# tx_v2.net
KiCad netlist of a schematic drawn in EAGLE
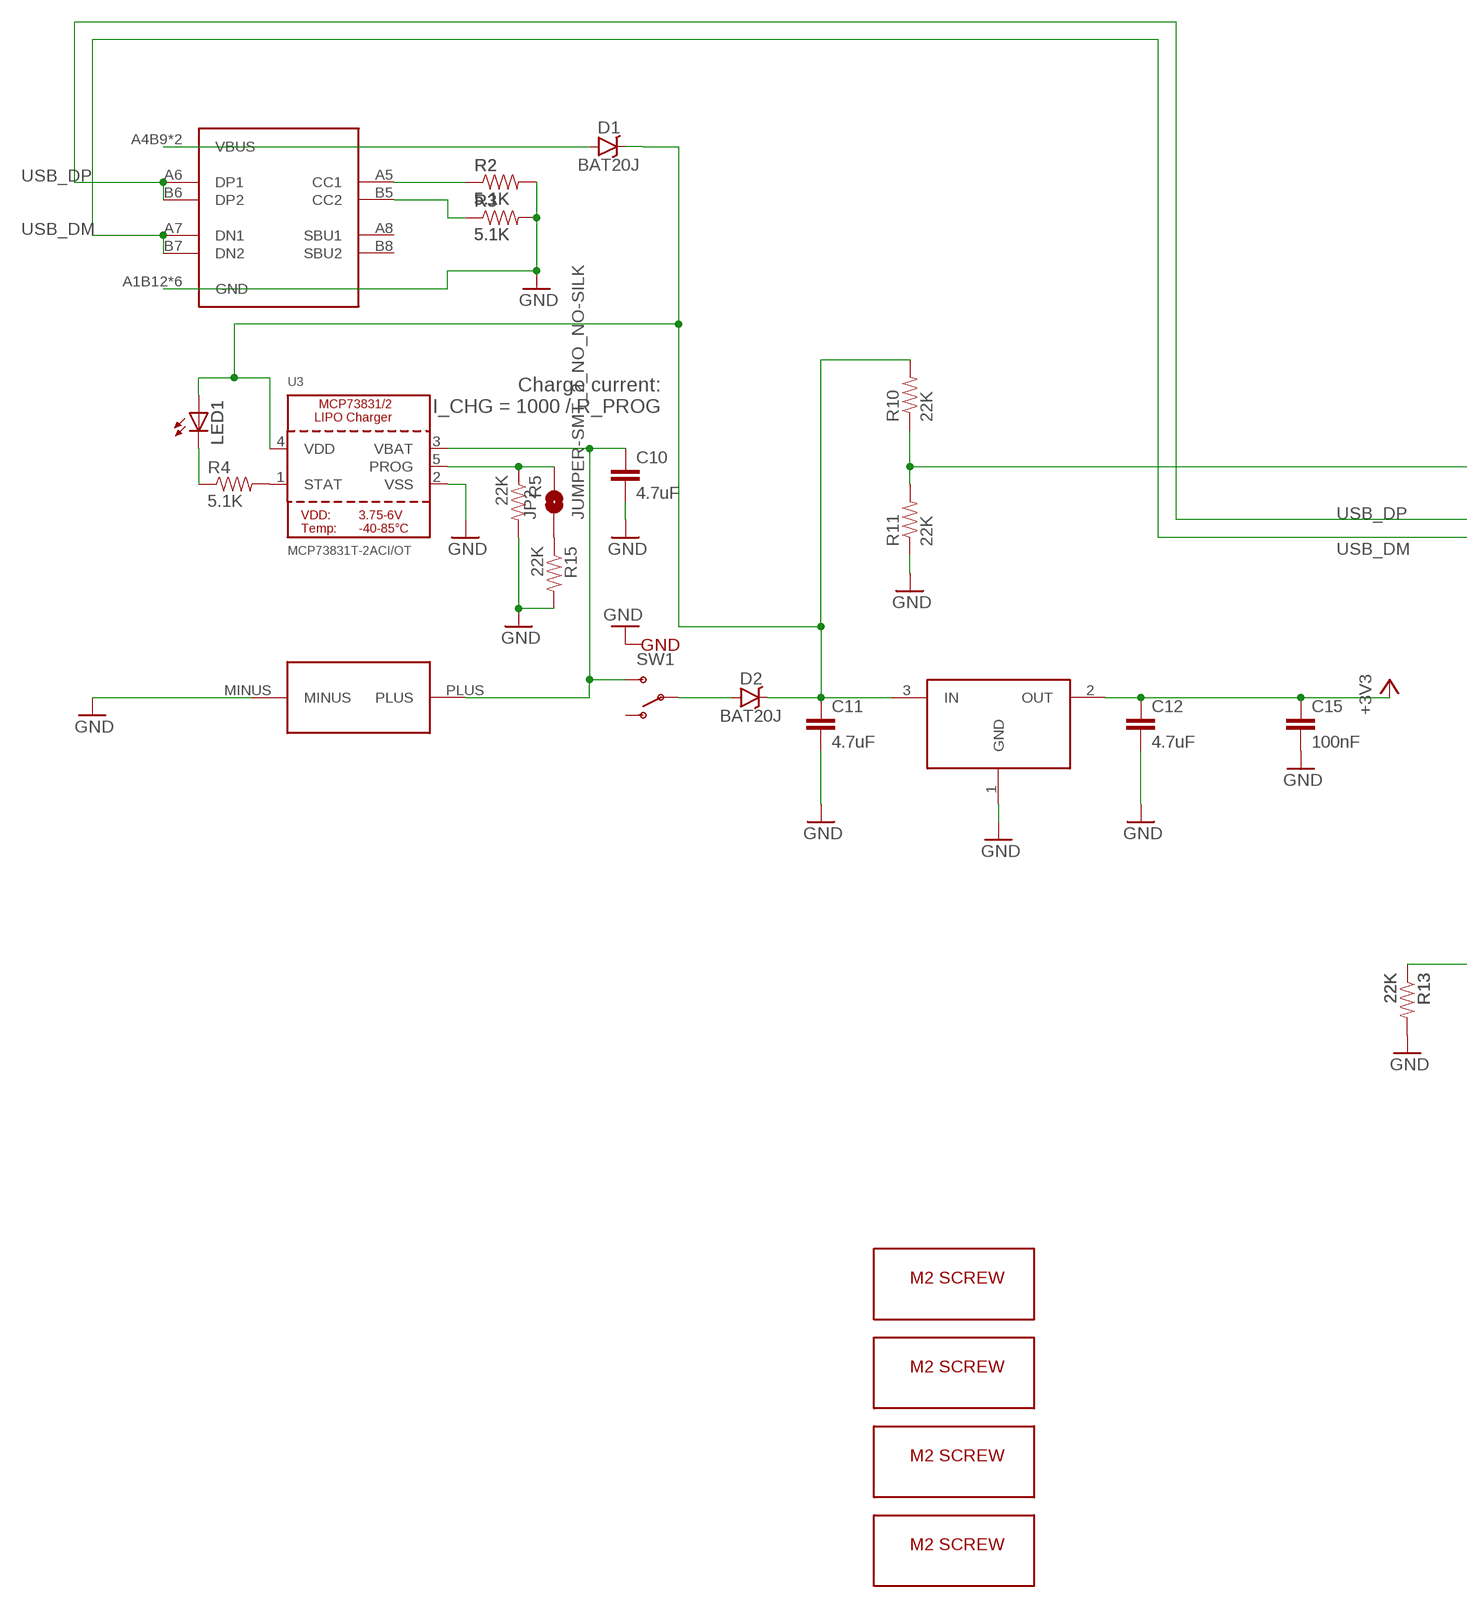
[diagram p0: schematic, sheet 1, part 1 of 2]
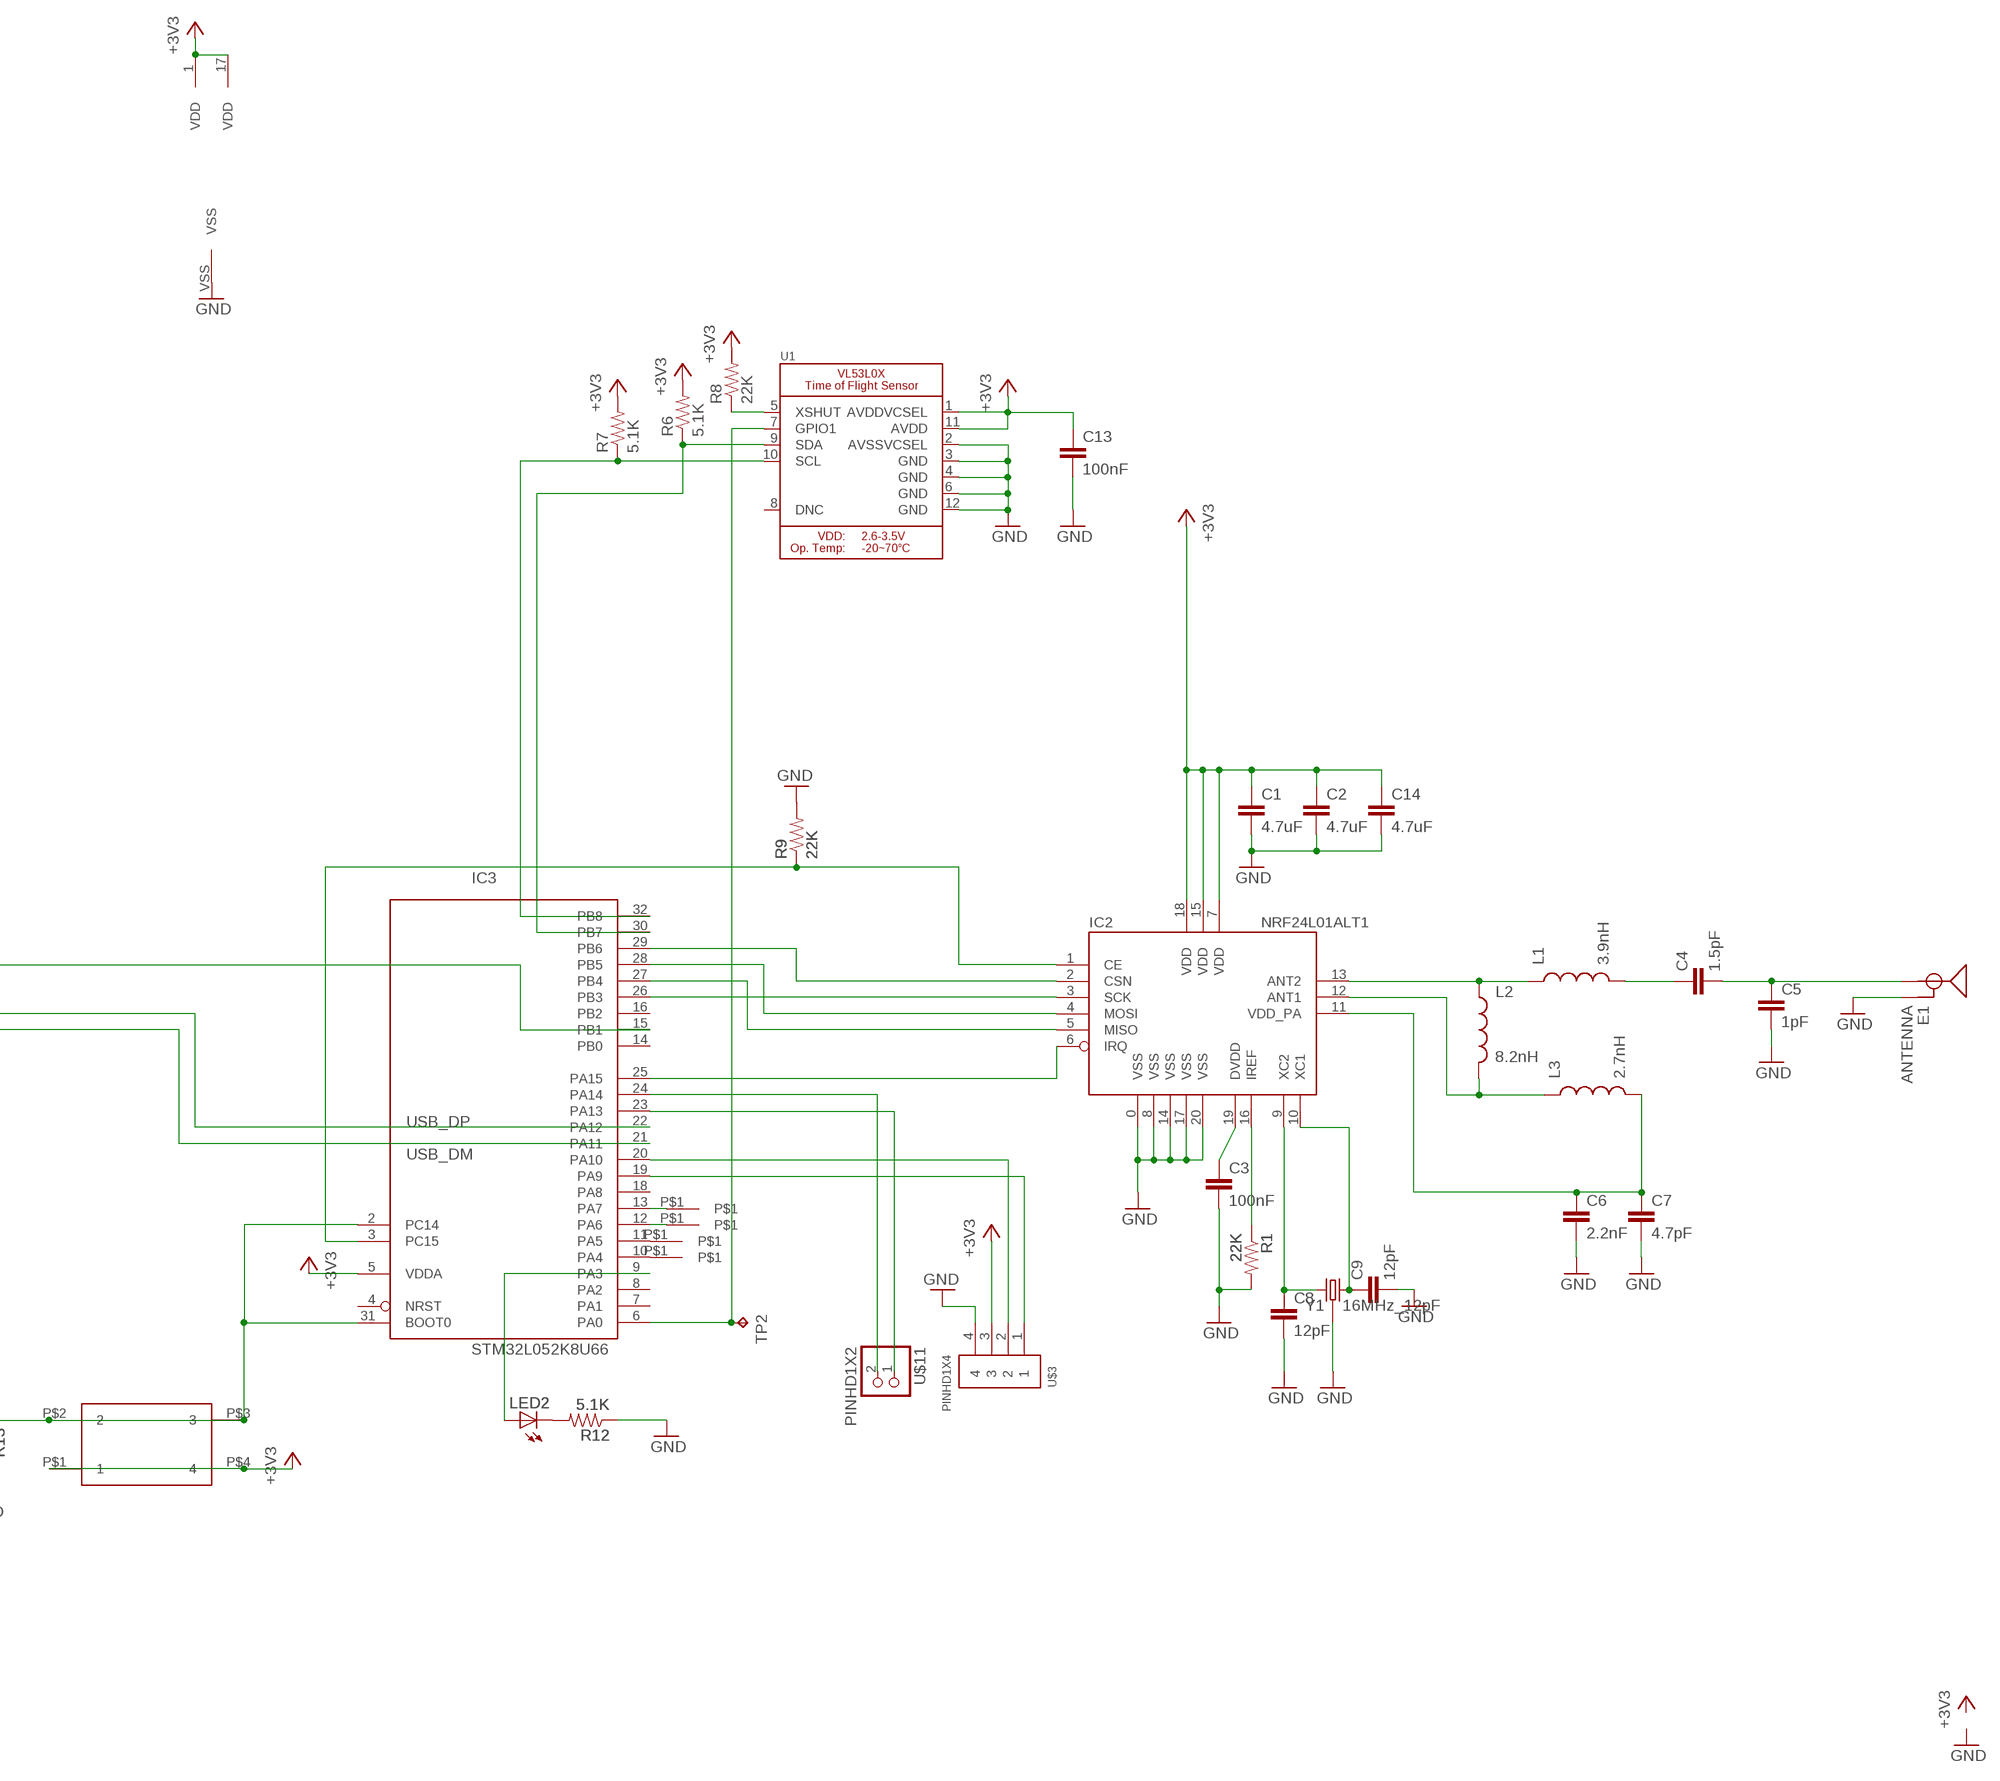
[diagram p1: schematic, sheet 1, part 2 of 2]

(export (version "E")
  (design (tool "Eeschema 10.0.6"))
  (components
    (comp (ref "C1")
      (value "4.7uF")
      (footprint "eagle-import:0805")
      (libsource (lib "eagle-import") (part "clock_CAP0805"))
    )
    (comp (ref "C2")
      (value "4.7uF")
      (footprint "eagle-import:0805")
      (libsource (lib "eagle-import") (part "clock_CAP0805"))
    )
    (comp (ref "C3")
      (value "100nF")
      (footprint "eagle-import:0805")
      (libsource (lib "eagle-import") (part "clock_CAP0805"))
    )
    (comp (ref "C4")
      (value "1.5pF")
      (footprint "eagle-import:0805")
      (libsource (lib "eagle-import") (part "clock_CAP0805"))
    )
    (comp (ref "C5")
      (value "1pF")
      (footprint "eagle-import:0805")
      (libsource (lib "eagle-import") (part "clock_CAP0805"))
    )
    (comp (ref "C6")
      (value "2.2nF")
      (footprint "eagle-import:0805")
      (libsource (lib "eagle-import") (part "clock_CAP0805"))
    )
    (comp (ref "C7")
      (value "4.7pF")
      (footprint "eagle-import:0805")
      (libsource (lib "eagle-import") (part "clock_CAP0805"))
    )
    (comp (ref "C8")
      (value "12pF")
      (footprint "eagle-import:0805")
      (libsource (lib "eagle-import") (part "clock_CAP0805"))
    )
    (comp (ref "C9")
      (value "12pF")
      (footprint "eagle-import:0805")
      (libsource (lib "eagle-import") (part "clock_CAP0805"))
    )
    (comp (ref "C10")
      (value "4.7uF")
      (footprint "eagle-import:0805")
      (libsource (lib "eagle-import") (part "CAP0805"))
    )
    (comp (ref "C11")
      (value "4.7uF")
      (footprint "eagle-import:0805")
      (libsource (lib "eagle-import") (part "clock_CAP0805"))
    )
    (comp (ref "C12")
      (value "4.7uF")
      (footprint "eagle-import:0805")
      (libsource (lib "eagle-import") (part "clock_CAP0805"))
    )
    (comp (ref "C13")
      (value "100nF")
      (footprint "eagle-import:0805")
      (libsource (lib "eagle-import") (part "clock_CAP0805"))
    )
    (comp (ref "C14")
      (value "4.7uF")
      (footprint "eagle-import:0805")
      (libsource (lib "eagle-import") (part "clock_CAP0805"))
    )
    (comp (ref "C15")
      (value "100nF")
      (footprint "eagle-import:0805")
      (libsource (lib "eagle-import") (part "clock_CAP0805"))
    )
    (comp (ref "D1")
      (value "BAT20J")
      (footprint "eagle-import:SOD-323")
      (libsource (lib "eagle-import") (part "DIODE-SCHOTTKY-BAT20J"))
    )
    (comp (ref "D2")
      (value "BAT20J")
      (footprint "eagle-import:SOD-323")
      (libsource (lib "eagle-import") (part "DIODE-SCHOTTKY-BAT20J"))
    )
    (comp (ref "E1")
      (value "ANTENNA")
      (footprint "eagle-import:TRACE_ANTENNA_2.4GHZ_25.7MM_TUNED")
      (libsource (lib "eagle-import") (part "ANTENNATRACE-TUNED"))
    )
    (comp (ref "IC2")
      (value "NRF24L01ALT1")
      (footprint "eagle-import:QFN20_ALT1")
      (libsource (lib "eagle-import") (part "NRF24L01ALT1"))
    )
    (comp (ref "IC3")
      (value "STM32L052K8U66")
      (footprint "eagle-import:UFQFPN32")
      (libsource (lib "eagle-import") (part "STM32L052K8U66"))
    )
    (comp (ref "JP2")
      (value "JUMPER-SMT_2_NO_NO-SILK")
      (footprint "eagle-import:SMT-JUMPER_2_NO_NO-SILK")
      (libsource (lib "eagle-import") (part "JUMPER-SMT_2_NO_NO-SILK"))
    )
    (comp (ref "L1")
      (value "3.9nH")
      (footprint "eagle-import:0805")
      (libsource (lib "eagle-import") (part "INDUCTOR0805"))
    )
    (comp (ref "L2")
      (value "8.2nH")
      (footprint "eagle-import:0805")
      (libsource (lib "eagle-import") (part "INDUCTOR0805"))
    )
    (comp (ref "L3")
      (value "2.7nH")
      (footprint "eagle-import:0805")
      (libsource (lib "eagle-import") (part "INDUCTOR0805"))
    )
    (comp (ref "LED1")
      (value "LEDCHIP-LED0805")
      (footprint "eagle-import:CHIP-LED0805")
      (libsource (lib "eagle-import") (part "LEDCHIP-LED0805"))
    )
    (comp (ref "LED2")
      (value "LEDCHIP-LED0805")
      (footprint "eagle-import:CHIP-LED0805")
      (libsource (lib "eagle-import") (part "LEDCHIP-LED0805"))
    )
    (comp (ref "R1")
      (value "22K")
      (footprint "eagle-import:0805")
      (libsource (lib "eagle-import") (part "joyAnalog_RESISTOR0805-RES"))
    )
    (comp (ref "R2")
      (value "5.1K")
      (footprint "eagle-import:0805")
      (libsource (lib "eagle-import") (part "joyAnalog_RESISTOR0805-RES"))
    )
    (comp (ref "R3")
      (value "5.1K")
      (footprint "eagle-import:0805")
      (libsource (lib "eagle-import") (part "joyAnalog_RESISTOR0805-RES"))
    )
    (comp (ref "R4")
      (value "5.1K")
      (footprint "eagle-import:0805")
      (libsource (lib "eagle-import") (part "RESISTOR0805-RES"))
    )
    (comp (ref "R5")
      (value "22K")
      (footprint "eagle-import:0805")
      (libsource (lib "eagle-import") (part "RESISTOR0805-RES"))
    )
    (comp (ref "R6")
      (value "5.1K")
      (footprint "eagle-import:0805")
      (libsource (lib "eagle-import") (part "RESISTOR0805-RES"))
    )
    (comp (ref "R7")
      (value "5.1K")
      (footprint "eagle-import:0805")
      (libsource (lib "eagle-import") (part "RESISTOR0805-RES"))
    )
    (comp (ref "R8")
      (value "22K")
      (footprint "eagle-import:0805")
      (libsource (lib "eagle-import") (part "RESISTOR0805-RES"))
    )
    (comp (ref "R9")
      (value "22K")
      (footprint "eagle-import:0805")
      (libsource (lib "eagle-import") (part "joyAnalog_RESISTOR0805-RES"))
    )
    (comp (ref "R10")
      (value "22K")
      (footprint "eagle-import:0805")
      (libsource (lib "eagle-import") (part "RESISTOR0805-RES"))
    )
    (comp (ref "R11")
      (value "22K")
      (footprint "eagle-import:0805")
      (libsource (lib "eagle-import") (part "RESISTOR0805-RES"))
    )
    (comp (ref "R12")
      (value "5.1K")
      (footprint "eagle-import:0805")
      (libsource (lib "eagle-import") (part "joyAnalog_RESISTOR0805-RES"))
    )
    (comp (ref "R13")
      (value "22K")
      (footprint "eagle-import:0805")
      (libsource (lib "eagle-import") (part "joyAnalog_RESISTOR0805-RES"))
    )
    (comp (ref "R15")
      (value "22K")
      (footprint "eagle-import:0805")
      (libsource (lib "eagle-import") (part "RESISTOR0805-RES"))
    )
    (comp (ref "SW1")
      (value "SWITCH-SPDTTDFGDFG")
      (footprint "eagle-import:SWITCH-SPST-SMD-A")
      (libsource (lib "eagle-import") (part "SWITCH-SPDTTDFGDFG"))
    )
    (comp (ref "SW2")
      (value "324_SW324_SWITCH_FOOT_HOLE")
      (footprint "eagle-import:342_SWICH_FOOT_HOLE")
      (libsource (lib "eagle-import") (part "324_SW324_SWITCH_FOOT_HOLE"))
    )
    (comp (ref "TP2")
      (value "TPTP10R")
      (footprint "eagle-import:TP10R")
      (libsource (lib "eagle-import") (part "TPTP10R"))
    )
    (comp (ref "U$1")
      (value "M2_SCREW_DEV")
      (footprint "eagle-import:M2_SCREW_FOOT")
      (libsource (lib "eagle-import") (part "M2_SCREW_DEV"))
    )
    (comp (ref "U$2")
      (value "HOT_SWAP_COIN_BAT")
      (footprint "eagle-import:COIN_BAT_HOTSWAP_SOCKET")
      (libsource (lib "eagle-import") (part "HOT_SWAP_COIN_BAT"))
    )
    (comp (ref "U$3")
      (value "PINHD1X4")
      (footprint "eagle-import:1X04-CLEANBIG")
      (libsource (lib "eagle-import") (part "PINHD1X4"))
    )
    (comp (ref "U$4")
      (value "TESTPAD")
      (footprint "eagle-import:TESTPAD")
      (libsource (lib "eagle-import") (part "TESTPAD"))
    )
    (comp (ref "U$5")
      (value "TESTPAD")
      (footprint "eagle-import:TESTPAD")
      (libsource (lib "eagle-import") (part "TESTPAD"))
    )
    (comp (ref "U$6")
      (value "TESTPAD")
      (footprint "eagle-import:TESTPAD")
      (libsource (lib "eagle-import") (part "TESTPAD"))
    )
    (comp (ref "U$7")
      (value "TESTPAD")
      (footprint "eagle-import:TESTPAD")
      (libsource (lib "eagle-import") (part "TESTPAD"))
    )
    (comp (ref "U$11")
      (value "PINHD1X2")
      (footprint "eagle-import:1X02")
      (libsource (lib "eagle-import") (part "PINHD1X2"))
    )
    (comp (ref "U$12")
      (value "M2_SCREW_DEV")
      (footprint "eagle-import:M2_SCREW_FOOT")
      (libsource (lib "eagle-import") (part "M2_SCREW_DEV"))
    )
    (comp (ref "U$13")
      (value "M2_SCREW_DEV")
      (footprint "eagle-import:M2_SCREW_FOOT")
      (libsource (lib "eagle-import") (part "M2_SCREW_DEV"))
    )
    (comp (ref "U$14")
      (value "M2_SCREW_DEV")
      (footprint "eagle-import:M2_SCREW_FOOT")
      (libsource (lib "eagle-import") (part "M2_SCREW_DEV"))
    )
    (comp (ref "U1")
      (value "VL53L0X")
      (footprint "eagle-import:LGA12_ST")
      (libsource (lib "eagle-import") (part "VL53L0X"))
    )
    (comp (ref "U2")
      (value "USBC_16P")
      (footprint "eagle-import:USBC_16P_FOOT")
      (libsource (lib "eagle-import") (part "USBC_16P"))
    )
    (comp (ref "U3")
      (value "MCP73831T-2ACI/OT")
      (footprint "eagle-import:SOT23-5")
      (libsource (lib "eagle-import") (part "MCP73831/2"))
    )
    (comp (ref "U4")
      (value "XC6206_DEV")
      (footprint "eagle-import:SOT23R_INFINEON")
      (libsource (lib "eagle-import") (part "XC6206_DEV"))
    )
    (comp (ref "Y1")
      (value "16MHz_12pF")
      (footprint "eagle-import:CRYSTAL-SMD-3.2X2.5MM")
      (libsource (lib "eagle-import") (part "CRYSTAL-26MHZSMD-3.2X2.5"))
    )
  )
  (nets
    (net (code "1") (name "+3V3") (class "Default")
      (node (ref "C1") (pin "1") (pinfunction "1_1") (pintype "passive"))
      (node (ref "C12") (pin "1") (pinfunction "1_1") (pintype "passive"))
      (node (ref "C13") (pin "1") (pinfunction "1_1") (pintype "passive"))
      (node (ref "C14") (pin "1") (pinfunction "1_1") (pintype "passive"))
      (node (ref "C15") (pin "1") (pinfunction "1_1") (pintype "passive"))
      (node (ref "C2") (pin "1") (pinfunction "1_1") (pintype "passive"))
      (node (ref "IC2") (pin "15") (pinfunction "VDD_15") (pintype "power_in"))
      (node (ref "IC2") (pin "18") (pinfunction "VDD_18") (pintype "power_in"))
      (node (ref "IC2") (pin "7") (pinfunction "VDD_7") (pintype "power_in"))
      (node (ref "IC3") (pin "1") (pinfunction "VDD_1") (pintype "power_in"))
      (node (ref "IC3") (pin "17") (pinfunction "VDD_17") (pintype "power_in"))
      (node (ref "IC3") (pin "5") (pinfunction "VDDA_5") (pintype "power_in"))
      (node (ref "R6") (pin "2") (pinfunction "2_2") (pintype "passive"))
      (node (ref "R7") (pin "2") (pinfunction "2_2") (pintype "passive"))
      (node (ref "R8") (pin "2") (pinfunction "2_2") (pintype "passive"))
      (node (ref "SW2") (pin "P$1") (pinfunction "1_P$1") (pintype "bidirectional"))
      (node (ref "SW2") (pin "P$4") (pinfunction "4_P$4") (pintype "bidirectional"))
      (node (ref "U$3") (pin "3") (pinfunction "3_3") (pintype "bidirectional"))
      (node (ref "U1") (pin "1") (pinfunction "AVDDVCSEL_1") (pintype "power_in"))
      (node (ref "U1") (pin "11") (pinfunction "AVDD_11") (pintype "power_in"))
      (node (ref "U4") (pin "2") (pinfunction "OUT_2") (pintype "bidirectional"))
    )
    (net (code "2") (name "/USB_DM") (class "Default")
      (node (ref "IC3") (pin "21") (pinfunction "PA11_21") (pintype "bidirectional"))
      (node (ref "U2") (pin "A7") (pinfunction "DN1_A7") (pintype "bidirectional"))
      (node (ref "U2") (pin "B7") (pinfunction "DN2_B7") (pintype "bidirectional"))
    )
    (net (code "3") (name "/USB_DP") (class "Default")
      (node (ref "IC3") (pin "22") (pinfunction "PA12_22") (pintype "bidirectional"))
      (node (ref "U2") (pin "A6") (pinfunction "DP1_A6") (pintype "bidirectional"))
      (node (ref "U2") (pin "B6") (pinfunction "DP2_B6") (pintype "bidirectional"))
    )
    (net (code "4") (name "GND") (class "Default")
      (node (ref "C1") (pin "2") (pinfunction "2_2") (pintype "passive"))
      (node (ref "C10") (pin "2") (pinfunction "2_2") (pintype "passive"))
      (node (ref "C11") (pin "2") (pinfunction "2_2") (pintype "passive"))
      (node (ref "C12") (pin "2") (pinfunction "2_2") (pintype "passive"))
      (node (ref "C13") (pin "2") (pinfunction "2_2") (pintype "passive"))
      (node (ref "C14") (pin "2") (pinfunction "2_2") (pintype "passive"))
      (node (ref "C15") (pin "2") (pinfunction "2_2") (pintype "passive"))
      (node (ref "C2") (pin "2") (pinfunction "2_2") (pintype "passive"))
      (node (ref "C3") (pin "2") (pinfunction "2_2") (pintype "passive"))
      (node (ref "C5") (pin "2") (pinfunction "2_2") (pintype "passive"))
      (node (ref "C6") (pin "2") (pinfunction "2_2") (pintype "passive"))
      (node (ref "C7") (pin "2") (pinfunction "2_2") (pintype "passive"))
      (node (ref "C8") (pin "2") (pinfunction "2_2") (pintype "passive"))
      (node (ref "C9") (pin "2") (pinfunction "2_2") (pintype "passive"))
      (node (ref "E1") (pin "GND") (pinfunction "GND_GND") (pintype "bidirectional"))
      (node (ref "E1") (pin "GND2") (pinfunction "GND_GND2") (pintype "bidirectional"))
      (node (ref "IC2") (pin "0") (pinfunction "VSS_0") (pintype "power_in"))
      (node (ref "IC2") (pin "14") (pinfunction "VSS_14") (pintype "power_in"))
      (node (ref "IC2") (pin "17") (pinfunction "VSS_17") (pintype "power_in"))
      (node (ref "IC2") (pin "20") (pinfunction "VSS_20") (pintype "power_in"))
      (node (ref "IC2") (pin "8") (pinfunction "VSS_8") (pintype "power_in"))
      (node (ref "IC3") (pin "VSS") (pinfunction "VSS_VSS") (pintype "power_in"))
      (node (ref "R1") (pin "2") (pinfunction "2_2") (pintype "passive"))
      (node (ref "R11") (pin "1") (pinfunction "1_1") (pintype "passive"))
      (node (ref "R12") (pin "1") (pinfunction "1_1") (pintype "passive"))
      (node (ref "R13") (pin "2") (pinfunction "2_2") (pintype "passive"))
      (node (ref "R15") (pin "2") (pinfunction "2_2") (pintype "passive"))
      (node (ref "R2") (pin "2") (pinfunction "2_2") (pintype "passive"))
      (node (ref "R3") (pin "2") (pinfunction "2_2") (pintype "passive"))
      (node (ref "R5") (pin "2") (pinfunction "2_2") (pintype "passive"))
      (node (ref "R9") (pin "2") (pinfunction "2_2") (pintype "passive"))
      (node (ref "SW1") (pin "G1") (pinfunction "GND_G1") (pintype "passive"))
      (node (ref "SW1") (pin "G2") (pinfunction "GND_G2") (pintype "passive"))
      (node (ref "SW1") (pin "G3") (pinfunction "GND_G3") (pintype "passive"))
      (node (ref "SW1") (pin "G4") (pinfunction "GND_G4") (pintype "passive"))
      (node (ref "U$2") (pin "MINUS") (pinfunction "MINUS_MINUS") (pintype "bidirectional"))
      (node (ref "U$3") (pin "4") (pinfunction "4_4") (pintype "bidirectional"))
      (node (ref "U1") (pin "12") (pinfunction "GND_12") (pintype "power_in"))
      (node (ref "U1") (pin "2") (pinfunction "AVSSVCSEL_2") (pintype "power_in"))
      (node (ref "U1") (pin "3") (pinfunction "GND_3") (pintype "power_in"))
      (node (ref "U1") (pin "4") (pinfunction "GND_4") (pintype "power_in"))
      (node (ref "U1") (pin "6") (pinfunction "GND_6") (pintype "power_in"))
      (node (ref "U2") (pin "A1B12") (pinfunction "GND_A1B12") (pintype "bidirectional"))
      (node (ref "U2") (pin "B11A12") (pinfunction "GND_B11A12") (pintype "bidirectional"))
      (node (ref "U2") (pin "P$13") (pinfunction "GND_P$13") (pintype "bidirectional"))
      (node (ref "U2") (pin "P$14") (pinfunction "GND_P$14") (pintype "bidirectional"))
      (node (ref "U2") (pin "P$15") (pinfunction "GND_P$15") (pintype "bidirectional"))
      (node (ref "U2") (pin "P$16") (pinfunction "GND_P$16") (pintype "bidirectional"))
      (node (ref "U3") (pin "2") (pinfunction "VSS_2") (pintype "power_in"))
      (node (ref "U4") (pin "1") (pinfunction "GND_1") (pintype "bidirectional"))
      (node (ref "Y1") (pin "2") (pinfunction "3_2") (pintype "passive"))
      (node (ref "Y1") (pin "4") (pinfunction "3_4") (pintype "passive"))
    )
    (net (code "5") (name "Net-(C4-Pad1)") (class "Default")
      (node (ref "C4") (pin "1") (pinfunction "1_1") (pintype "passive"))
      (node (ref "L1") (pin "2") (pinfunction "2_2") (pintype "passive"))
    )
    (net (code "6") (name "Net-(D1-PadA)") (class "Default")
      (node (ref "D1") (pin "A") (pinfunction "A_A") (pintype "passive"))
      (node (ref "U2") (pin "A4B9") (pinfunction "VBUS_A4B9") (pintype "bidirectional"))
      (node (ref "U2") (pin "B4A9") (pinfunction "VBUS_B4A9") (pintype "bidirectional"))
    )
    (net (code "7") (name "Net-(E1-SIGNAL)") (class "Default")
      (node (ref "C4") (pin "2") (pinfunction "2_2") (pintype "passive"))
      (node (ref "C5") (pin "1") (pinfunction "1_1") (pintype "passive"))
      (node (ref "E1") (pin "ANT") (pinfunction "SIGNAL_ANT") (pintype "bidirectional"))
    )
    (net (code "8") (name "Net-(IC2-ANT1)") (class "Default")
      (node (ref "IC2") (pin "12") (pinfunction "ANT1_12") (pintype "output"))
      (node (ref "L2") (pin "2") (pinfunction "2_2") (pintype "passive"))
      (node (ref "L3") (pin "1") (pinfunction "1_1") (pintype "passive"))
    )
    (net (code "9") (name "Net-(IC2-ANT2)") (class "Default")
      (node (ref "IC2") (pin "13") (pinfunction "ANT2_13") (pintype "output"))
      (node (ref "L1") (pin "1") (pinfunction "1_1") (pintype "passive"))
      (node (ref "L2") (pin "1") (pinfunction "1_1") (pintype "passive"))
    )
    (net (code "10") (name "Net-(IC2-CE)") (class "Default")
      (node (ref "IC2") (pin "1") (pinfunction "CE_1") (pintype "input"))
      (node (ref "IC3") (pin "3") (pinfunction "PC15_3") (pintype "bidirectional"))
      (node (ref "R9") (pin "1") (pinfunction "1_1") (pintype "passive"))
    )
    (net (code "11") (name "Net-(IC2-CSN)") (class "Default")
      (node (ref "IC2") (pin "2") (pinfunction "CSN_2") (pintype "input"))
      (node (ref "IC3") (pin "29") (pinfunction "PB6_29") (pintype "bidirectional"))
    )
    (net (code "12") (name "Net-(IC2-DVDD)") (class "Default")
      (node (ref "C3") (pin "1") (pinfunction "1_1") (pintype "passive"))
      (node (ref "IC2") (pin "19") (pinfunction "DVDD_19") (pintype "power_in"))
    )
    (net (code "13") (name "Net-(IC2-IREF)") (class "Default")
      (node (ref "IC2") (pin "16") (pinfunction "IREF_16") (pintype "input"))
      (node (ref "R1") (pin "1") (pinfunction "1_1") (pintype "passive"))
    )
    (net (code "14") (name "Net-(IC2-IRQ)") (class "Default")
      (node (ref "IC2") (pin "6") (pinfunction "IRQ_6") (pintype "output"))
      (node (ref "IC3") (pin "25") (pinfunction "PA15_25") (pintype "bidirectional"))
    )
    (net (code "15") (name "Net-(IC2-MISO)") (class "Default")
      (node (ref "IC2") (pin "5") (pinfunction "MISO_5") (pintype "output"))
      (node (ref "IC3") (pin "27") (pinfunction "PB4_27") (pintype "bidirectional"))
    )
    (net (code "16") (name "Net-(IC2-MOSI)") (class "Default")
      (node (ref "IC2") (pin "4") (pinfunction "MOSI_4") (pintype "input"))
      (node (ref "IC3") (pin "28") (pinfunction "PB5_28") (pintype "bidirectional"))
    )
    (net (code "17") (name "Net-(IC2-SCK)") (class "Default")
      (node (ref "IC2") (pin "3") (pinfunction "SCK_3") (pintype "input"))
      (node (ref "IC3") (pin "26") (pinfunction "PB3_26") (pintype "bidirectional"))
    )
    (net (code "18") (name "Net-(IC2-VDD_PA)") (class "Default")
      (node (ref "C6") (pin "1") (pinfunction "1_1") (pintype "passive"))
      (node (ref "C7") (pin "1") (pinfunction "1_1") (pintype "passive"))
      (node (ref "IC2") (pin "11") (pinfunction "VDD_PA_11") (pintype "power_in"))
      (node (ref "L3") (pin "2") (pinfunction "2_2") (pintype "passive"))
    )
    (net (code "19") (name "Net-(IC2-XC1)") (class "Default")
      (node (ref "C9") (pin "1") (pinfunction "1_1") (pintype "passive"))
      (node (ref "IC2") (pin "10") (pinfunction "XC1_10") (pintype "input"))
      (node (ref "Y1") (pin "3") (pinfunction "2_3") (pintype "passive"))
    )
    (net (code "20") (name "Net-(IC2-XC2)") (class "Default")
      (node (ref "C8") (pin "1") (pinfunction "1_1") (pintype "passive"))
      (node (ref "IC2") (pin "9") (pinfunction "XC2_9") (pintype "input"))
      (node (ref "Y1") (pin "1") (pinfunction "1_1") (pintype "passive"))
    )
    (net (code "21") (name "Net-(IC3A-BOOT0)") (class "Default")
      (node (ref "IC3") (pin "2") (pinfunction "PC14_2") (pintype "bidirectional"))
      (node (ref "IC3") (pin "31") (pinfunction "BOOT0_31") (pintype "input"))
      (node (ref "R13") (pin "1") (pinfunction "1_1") (pintype "passive"))
      (node (ref "SW2") (pin "P$2") (pinfunction "2_P$2") (pintype "bidirectional"))
      (node (ref "SW2") (pin "P$3") (pinfunction "3_P$3") (pintype "bidirectional"))
    )
    (net (code "22") (name "Net-(IC3A-PA0)") (class "Default")
      (node (ref "IC3") (pin "6") (pinfunction "PA0_6") (pintype "bidirectional"))
      (node (ref "TP2") (pin "TP") (pinfunction "TP_TP") (pintype "input"))
      (node (ref "U1") (pin "7") (pinfunction "GPIO1_7") (pintype "output"))
    )
    (net (code "23") (name "Net-(IC3A-PA3)") (class "Default")
      (node (ref "IC3") (pin "9") (pinfunction "PA3_9") (pintype "bidirectional"))
      (node (ref "LED2") (pin "A") (pinfunction "A_A") (pintype "passive"))
    )
    (net (code "24") (name "Net-(IC3A-PA4)") (class "Default")
      (node (ref "IC3") (pin "10") (pinfunction "PA4_10") (pintype "bidirectional"))
      (node (ref "U$5") (pin "P$1") (pinfunction "P$1_P$1") (pintype "bidirectional"))
    )
    (net (code "25") (name "Net-(IC3A-PA5)") (class "Default")
      (node (ref "IC3") (pin "11") (pinfunction "PA5_11") (pintype "bidirectional"))
      (node (ref "U$4") (pin "P$1") (pinfunction "P$1_P$1") (pintype "bidirectional"))
    )
    (net (code "26") (name "Net-(IC3A-PA6)") (class "Default")
      (node (ref "IC3") (pin "12") (pinfunction "PA6_12") (pintype "bidirectional"))
      (node (ref "U$7") (pin "P$1") (pinfunction "P$1_P$1") (pintype "bidirectional"))
    )
    (net (code "27") (name "Net-(IC3A-PA7)") (class "Default")
      (node (ref "IC3") (pin "13") (pinfunction "PA7_13") (pintype "bidirectional"))
      (node (ref "U$6") (pin "P$1") (pinfunction "P$1_P$1") (pintype "bidirectional"))
    )
    (net (code "28") (name "Net-(IC3A-PA9)") (class "Default")
      (node (ref "IC3") (pin "19") (pinfunction "PA9_19") (pintype "bidirectional"))
      (node (ref "U$3") (pin "1") (pinfunction "1_1") (pintype "bidirectional"))
    )
    (net (code "29") (name "Net-(IC3A-PA10)") (class "Default")
      (node (ref "IC3") (pin "20") (pinfunction "PA10_20") (pintype "bidirectional"))
      (node (ref "U$3") (pin "2") (pinfunction "2_2") (pintype "bidirectional"))
    )
    (net (code "30") (name "Net-(IC3A-PA13)") (class "Default")
      (node (ref "IC3") (pin "23") (pinfunction "PA13_23") (pintype "bidirectional"))
      (node (ref "U$11") (pin "1") (pinfunction "1_1") (pintype "passive"))
    )
    (net (code "31") (name "Net-(IC3A-PA14)") (class "Default")
      (node (ref "IC3") (pin "24") (pinfunction "PA14_24") (pintype "bidirectional"))
      (node (ref "U$11") (pin "2") (pinfunction "2_2") (pintype "passive"))
    )
    (net (code "32") (name "Net-(IC3A-PB1)") (class "Default")
      (node (ref "IC3") (pin "15") (pinfunction "PB1_15") (pintype "bidirectional"))
      (node (ref "R10") (pin "1") (pinfunction "1_1") (pintype "passive"))
      (node (ref "R11") (pin "2") (pinfunction "2_2") (pintype "passive"))
    )
    (net (code "33") (name "Net-(IC3A-PB7)") (class "Default")
      (node (ref "IC3") (pin "30") (pinfunction "PB7_30") (pintype "bidirectional"))
      (node (ref "R6") (pin "1") (pinfunction "1_1") (pintype "passive"))
      (node (ref "U1") (pin "9") (pinfunction "SDA_9") (pintype "open_collector"))
    )
    (net (code "34") (name "Net-(IC3A-PB8)") (class "Default")
      (node (ref "IC3") (pin "32") (pinfunction "PB8_32") (pintype "bidirectional"))
      (node (ref "R7") (pin "1") (pinfunction "1_1") (pintype "passive"))
      (node (ref "U1") (pin "10") (pinfunction "SCL_10") (pintype "open_collector"))
    )
    (net (code "35") (name "Net-(JP2-Pad1)") (class "Default")
      (node (ref "JP2") (pin "1") (pinfunction "1_1") (pintype "passive"))
      (node (ref "R15") (pin "1") (pinfunction "1_1") (pintype "passive"))
    )
    (net (code "36") (name "Net-(LED1-PadC)") (class "Default")
      (node (ref "LED1") (pin "C") (pinfunction "C_C") (pintype "passive"))
      (node (ref "R4") (pin "1") (pinfunction "1_1") (pintype "passive"))
    )
    (net (code "37") (name "Net-(LED2-PadC)") (class "Default")
      (node (ref "LED2") (pin "C") (pinfunction "C_C") (pintype "passive"))
      (node (ref "R12") (pin "2") (pinfunction "2_2") (pintype "passive"))
    )
    (net (code "38") (name "Net-(SW1-P)") (class "Default")
      (node (ref "D2") (pin "A") (pinfunction "A_A") (pintype "passive"))
      (node (ref "SW1") (pin "2") (pinfunction "P_2") (pintype "passive"))
    )
    (net (code "39") (name "Net-(SW1-S)") (class "Default")
      (node (ref "C10") (pin "1") (pinfunction "1_1") (pintype "passive"))
      (node (ref "SW1") (pin "3") (pinfunction "S_3") (pintype "passive"))
      (node (ref "U$2") (pin "PLUS") (pinfunction "PLUS_PLUS") (pintype "bidirectional"))
      (node (ref "U3") (pin "3") (pinfunction "VBAT_3") (pintype "power_in"))
    )
    (net (code "40") (name "Net-(U1-XSHUT)") (class "Default")
      (node (ref "R8") (pin "1") (pinfunction "1_1") (pintype "passive"))
      (node (ref "U1") (pin "5") (pinfunction "XSHUT_5") (pintype "input"))
    )
    (net (code "41") (name "Net-(U2-CC1)") (class "Default")
      (node (ref "R2") (pin "1") (pinfunction "1_1") (pintype "passive"))
      (node (ref "U2") (pin "A5") (pinfunction "CC1_A5") (pintype "bidirectional"))
    )
    (net (code "42") (name "Net-(U2-CC2)") (class "Default")
      (node (ref "R3") (pin "1") (pinfunction "1_1") (pintype "passive"))
      (node (ref "U2") (pin "B5") (pinfunction "CC2_B5") (pintype "bidirectional"))
    )
    (net (code "43") (name "Net-(U3-PROG)") (class "Default")
      (node (ref "JP2") (pin "2") (pinfunction "2_2") (pintype "passive"))
      (node (ref "R5") (pin "1") (pinfunction "1_1") (pintype "passive"))
      (node (ref "U3") (pin "5") (pinfunction "PROG_5") (pintype "input"))
    )
    (net (code "44") (name "Net-(U3-STAT)") (class "Default")
      (node (ref "R4") (pin "2") (pinfunction "2_2") (pintype "passive"))
      (node (ref "U3") (pin "1") (pinfunction "STAT_1") (pintype "output"))
    )
    (net (code "45") (name "Net-(U3-VDD)") (class "Default")
      (node (ref "C11") (pin "1") (pinfunction "1_1") (pintype "passive"))
      (node (ref "D1") (pin "C") (pinfunction "C_C") (pintype "passive"))
      (node (ref "D2") (pin "C") (pinfunction "C_C") (pintype "passive"))
      (node (ref "LED1") (pin "A") (pinfunction "A_A") (pintype "passive"))
      (node (ref "R10") (pin "2") (pinfunction "2_2") (pintype "passive"))
      (node (ref "U3") (pin "4") (pinfunction "VDD_4") (pintype "power_in"))
      (node (ref "U4") (pin "3") (pinfunction "IN_3") (pintype "bidirectional"))
    )
    (net (code "46") (name "unconnected-(IC3A-NRST-Pad4)") (class "Default")
      (node (ref "IC3") (pin "4") (pinfunction "NRST_4") (pintype "bidirectional"))
    )
    (net (code "47") (name "unconnected-(IC3A-PA1-Pad7)") (class "Default")
      (node (ref "IC3") (pin "7") (pinfunction "PA1_7") (pintype "bidirectional"))
    )
    (net (code "48") (name "unconnected-(IC3A-PA2-Pad8)") (class "Default")
      (node (ref "IC3") (pin "8") (pinfunction "PA2_8") (pintype "bidirectional"))
    )
    (net (code "49") (name "unconnected-(IC3A-PA8-Pad18)") (class "Default")
      (node (ref "IC3") (pin "18") (pinfunction "PA8_18") (pintype "bidirectional"))
    )
    (net (code "50") (name "unconnected-(IC3A-PB0-Pad14)") (class "Default")
      (node (ref "IC3") (pin "14") (pinfunction "PB0_14") (pintype "bidirectional"))
    )
    (net (code "51") (name "unconnected-(IC3A-PB2-Pad16)") (class "Default")
      (node (ref "IC3") (pin "16") (pinfunction "PB2_16") (pintype "bidirectional"))
    )
    (net (code "52") (name "unconnected-(SW1-O-Pad1)") (class "Default")
      (node (ref "SW1") (pin "1") (pinfunction "O_1") (pintype "passive"))
    )
    (net (code "53") (name "unconnected-(U1-DNC-Pad8)") (class "Default")
      (node (ref "U1") (pin "8") (pinfunction "DNC_8") (pintype "no_connect"))
    )
    (net (code "54") (name "unconnected-(U2-SBU1-PadA8)") (class "Default")
      (node (ref "U2") (pin "A8") (pinfunction "SBU1_A8") (pintype "bidirectional"))
    )
    (net (code "55") (name "unconnected-(U2-SBU2-PadB8)") (class "Default")
      (node (ref "U2") (pin "B8") (pinfunction "SBU2_B8") (pintype "bidirectional"))
    )
  )
)
